# main_bottom.net
KiCad netlist of a schematic drawn in EAGLE
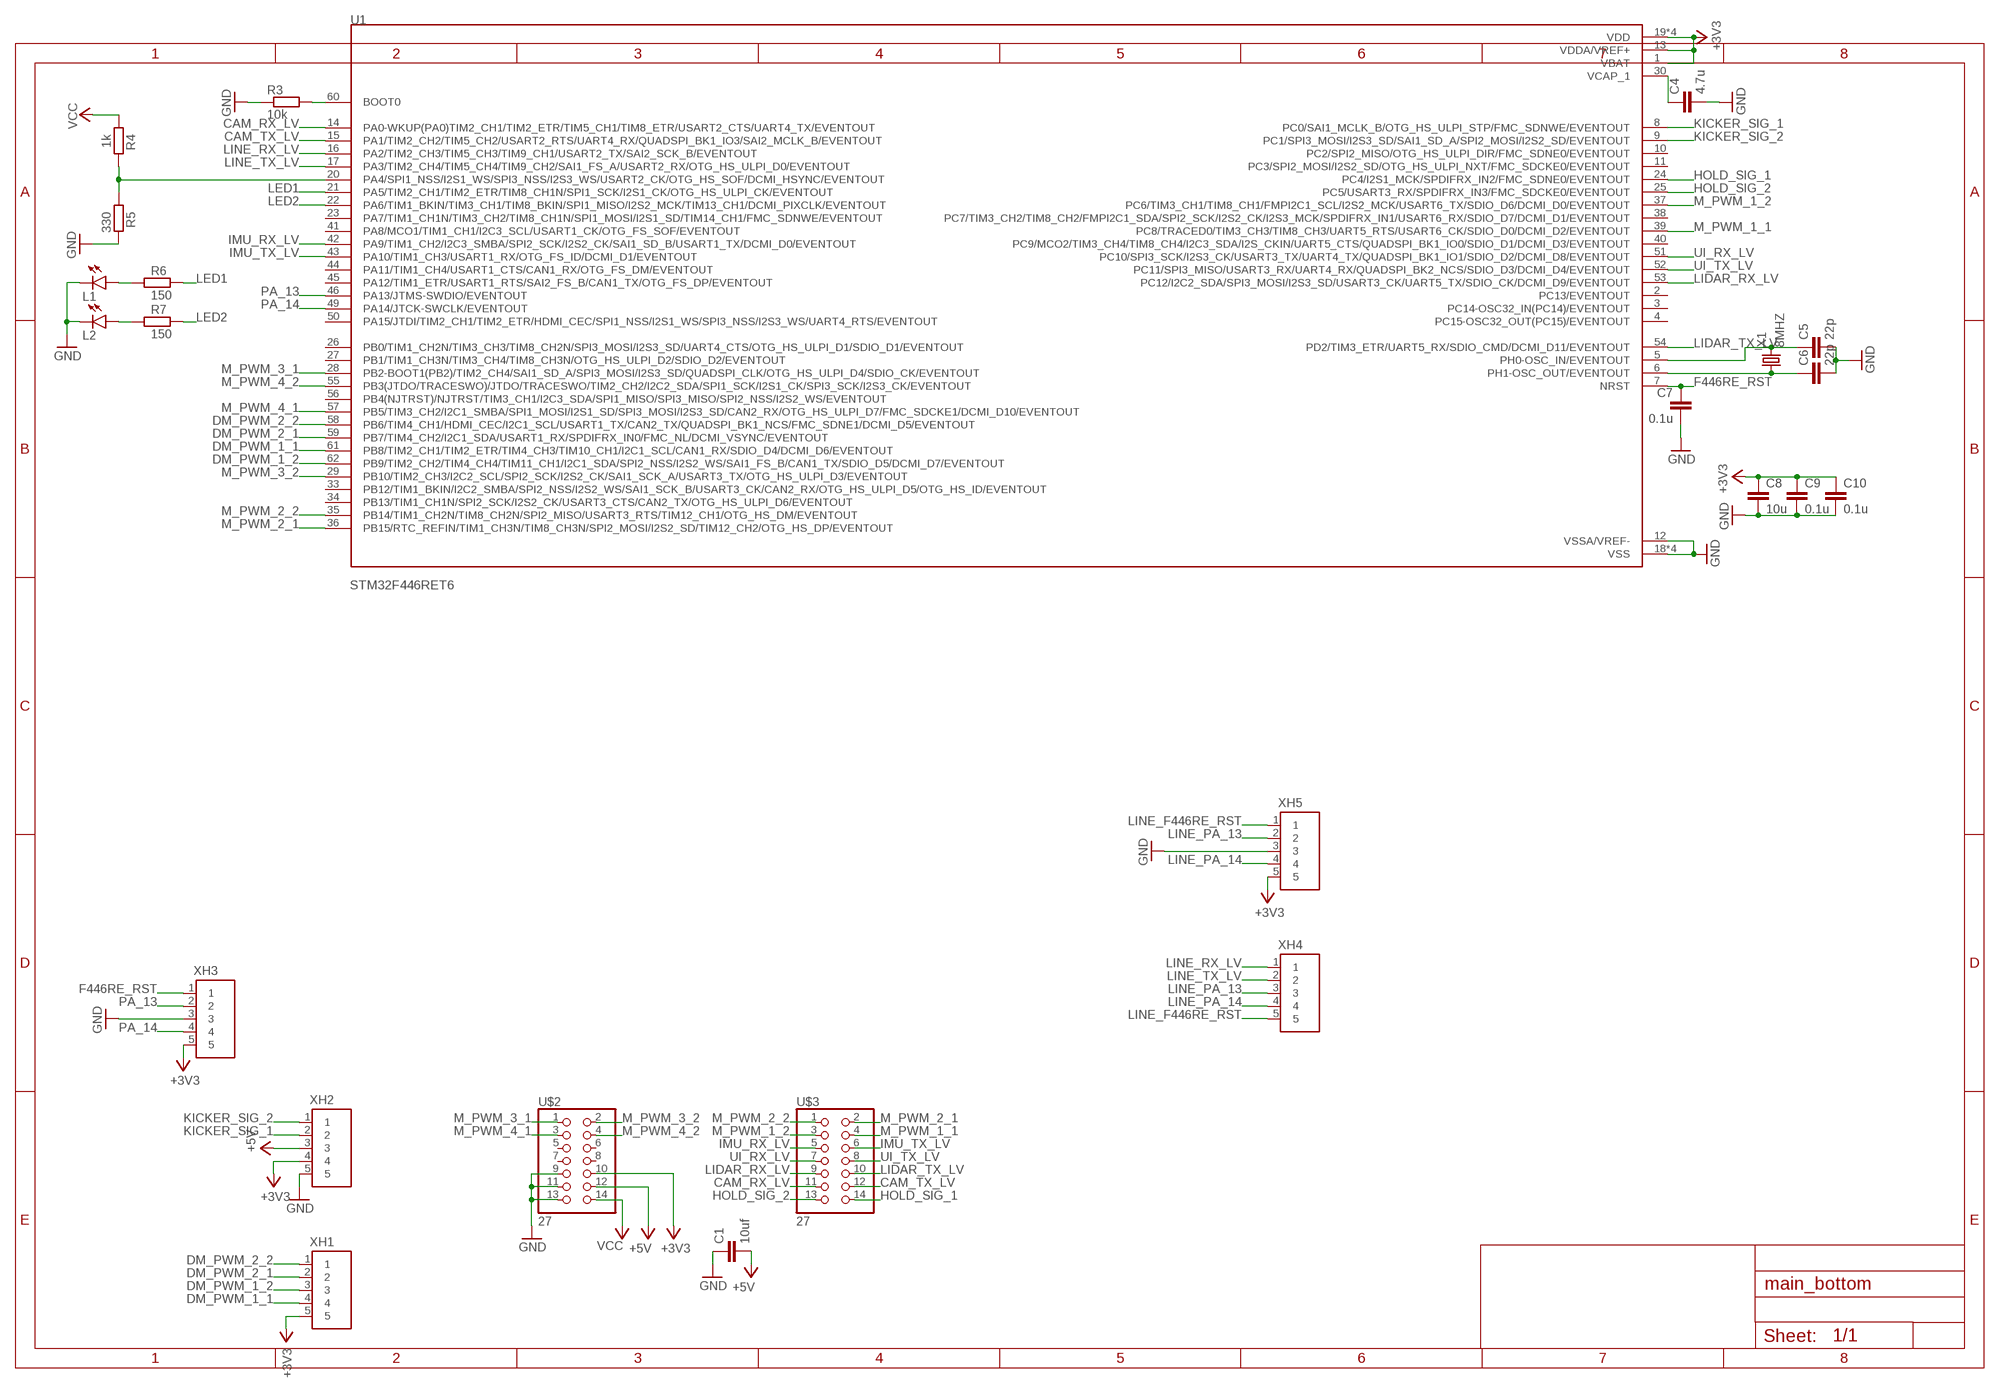
[diagram p0: schematic, sheet 1]

(export (version "E")
  (design (tool "Eeschema 10.0.6"))
  (components
    (comp (ref "C1")
      (value "10uf")
      (footprint "eagle-import:C0805")
      (libsource (lib "eagle-import") (part "C-EUC0805"))
    )
    (comp (ref "C4")
      (value "4.7u")
      (footprint "eagle-import:C0603")
      (libsource (lib "eagle-import") (part "C-EUC0603"))
    )
    (comp (ref "C5")
      (value "22p")
      (footprint "eagle-import:C0603")
      (libsource (lib "eagle-import") (part "C-EUC0603"))
    )
    (comp (ref "C6")
      (value "22p")
      (footprint "eagle-import:C0603")
      (libsource (lib "eagle-import") (part "C-EUC0603"))
    )
    (comp (ref "C7")
      (value "0.1u")
      (footprint "eagle-import:C0603")
      (libsource (lib "eagle-import") (part "C-EUC0603"))
    )
    (comp (ref "C8")
      (value "10u")
      (footprint "eagle-import:C0805")
      (libsource (lib "eagle-import") (part "C-EUC0805"))
    )
    (comp (ref "C9")
      (value "0.1u")
      (footprint "eagle-import:C0603")
      (libsource (lib "eagle-import") (part "C-EUC0603"))
    )
    (comp (ref "C10")
      (value "0.1u")
      (footprint "eagle-import:C0603")
      (libsource (lib "eagle-import") (part "C-EUC0603"))
    )
    (comp (ref "L1")
      (value "SML-E12P8WT86")
      (footprint "eagle-import:LED_SML-LXFM0603SIC-TR")
      (libsource (lib "eagle-import") (part "SML-E12P8WT86"))
    )
    (comp (ref "L2")
      (value "SML-E12P8WT86")
      (footprint "eagle-import:LED_SML-LXFM0603SIC-TR")
      (libsource (lib "eagle-import") (part "SML-E12P8WT86"))
    )
    (comp (ref "R3")
      (value "10k")
      (footprint "eagle-import:R0603")
      (libsource (lib "eagle-import") (part "R-EU_R0603"))
    )
    (comp (ref "R4")
      (value "1k")
      (footprint "eagle-import:R0603")
      (libsource (lib "eagle-import") (part "R-EU_R0603"))
    )
    (comp (ref "R5")
      (value "330")
      (footprint "eagle-import:R0603")
      (libsource (lib "eagle-import") (part "R-EU_R0603"))
    )
    (comp (ref "R6")
      (value "150")
      (footprint "eagle-import:R0603")
      (libsource (lib "eagle-import") (part "R-EU_R0603"))
    )
    (comp (ref "R7")
      (value "150")
      (footprint "eagle-import:R0603")
      (libsource (lib "eagle-import") (part "R-EU_R0603"))
    )
    (comp (ref "U$2")
      (value "27")
      (footprint "eagle-import:2_7")
      (libsource (lib "eagle-import") (part "27"))
    )
    (comp (ref "U$3")
      (value "27")
      (footprint "eagle-import:2_7")
      (libsource (lib "eagle-import") (part "27"))
    )
    (comp (ref "U1")
      (value "STM32F446RET6")
      (footprint "eagle-import:QFP50P1200X1200X160-64N")
      (fields (field (name "MF") "STMicroelectronics"))
      (libsource (lib "eagle-import") (part "STM32F446RET6"))
    )
    (comp (ref "X1")
      (value "8MHZ")
      (footprint "eagle-import:16MHZ")
      (libsource (lib "eagle-import") (part "16MHZ"))
    )
    (comp (ref "XH1")
      (value "S5B")
      (footprint "eagle-import:S5B")
      (libsource (lib "eagle-import") (part "S5B"))
    )
    (comp (ref "XH2")
      (value "S5B")
      (footprint "eagle-import:S5B")
      (libsource (lib "eagle-import") (part "S5B"))
    )
    (comp (ref "XH3")
      (value "S5B")
      (footprint "eagle-import:S5B")
      (libsource (lib "eagle-import") (part "S5B"))
    )
    (comp (ref "XH4")
      (value "S5B")
      (footprint "eagle-import:S5B")
      (libsource (lib "eagle-import") (part "S5B"))
    )
    (comp (ref "XH5")
      (value "S5B")
      (footprint "eagle-import:S5B")
      (libsource (lib "eagle-import") (part "S5B"))
    )
  )
  (nets
    (net (code "1") (name "+3V3") (class "Default")
      (node (ref "C10") (pin "1") (pinfunction "1_1") (pintype "passive"))
      (node (ref "C8") (pin "1") (pinfunction "1_1") (pintype "passive"))
      (node (ref "C9") (pin "1") (pinfunction "1_1") (pintype "passive"))
      (node (ref "U$2") (pin "10") (pinfunction "10_10") (pintype "passive"))
      (node (ref "U1") (pin "1") (pinfunction "VBAT_1") (pintype "power_in"))
      (node (ref "U1") (pin "13") (pinfunction "VDDA/VREF+_13") (pintype "power_in"))
      (node (ref "U1") (pin "19") (pinfunction "VDD_19") (pintype "power_in"))
      (node (ref "U1") (pin "32") (pinfunction "VDD_32") (pintype "power_in"))
      (node (ref "U1") (pin "48") (pinfunction "VDD_48") (pintype "power_in"))
      (node (ref "U1") (pin "64") (pinfunction "VDD_64") (pintype "power_in"))
      (node (ref "XH1") (pin "5") (pinfunction "5_5") (pintype "bidirectional"))
      (node (ref "XH2") (pin "4") (pinfunction "4_4") (pintype "bidirectional"))
      (node (ref "XH3") (pin "5") (pinfunction "5_5") (pintype "bidirectional"))
      (node (ref "XH5") (pin "5") (pinfunction "5_5") (pintype "bidirectional"))
    )
    (net (code "2") (name "+5V") (class "Default")
      (node (ref "C1") (pin "2") (pinfunction "2_2") (pintype "passive"))
      (node (ref "U$2") (pin "12") (pinfunction "12_12") (pintype "passive"))
      (node (ref "XH2") (pin "3") (pinfunction "3_3") (pintype "bidirectional"))
    )
    (net (code "3") (name "/CAM_RX_LV") (class "Default")
      (node (ref "U$3") (pin "11") (pinfunction "11_11") (pintype "passive"))
      (node (ref "U1") (pin "14") (pinfunction "PA0-WKUP(PA0)TIM2_CH1/TIM2_ETR/TIM5_CH1/TIM8_ETR/USART2_CTS/UART4_TX/EVENTOUT_14") (pintype "bidirectional"))
    )
    (net (code "4") (name "/CAM_TX_LV") (class "Default")
      (node (ref "U$3") (pin "12") (pinfunction "12_12") (pintype "passive"))
      (node (ref "U1") (pin "15") (pinfunction "PA1/TIM2_CH2/TIM5_CH2/USART2_RTS/UART4_RX/QUADSPI_BK1_IO3/SAI2_MCLK_B/EVENTOUT_15") (pintype "bidirectional"))
    )
    (net (code "5") (name "/DM_PWM_1_1") (class "Default")
      (node (ref "U1") (pin "61") (pinfunction "PB8/TIM2_CH1/TIM2_ETR/TIM4_CH3/TIM10_CH1/I2C1_SCL/CAN1_RX/SDIO_D4/DCMI_D6/EVENTOUT_61") (pintype "bidirectional"))
      (node (ref "XH1") (pin "4") (pinfunction "4_4") (pintype "bidirectional"))
    )
    (net (code "6") (name "/DM_PWM_1_2") (class "Default")
      (node (ref "U1") (pin "62") (pinfunction "PB9/TIM2_CH2/TIM4_CH4/TIM11_CH1/I2C1_SDA/SPI2_NSS/I2S2_WS/SAI1_FS_B/CAN1_TX/SDIO_D5/DCMI_D7/EVENTOUT_62") (pintype "bidirectional"))
      (node (ref "XH1") (pin "3") (pinfunction "3_3") (pintype "bidirectional"))
    )
    (net (code "7") (name "/DM_PWM_2_1") (class "Default")
      (node (ref "U1") (pin "59") (pinfunction "PB7/TIM4_CH2/I2C1_SDA/USART1_RX/SPDIFRX_IN0/FMC_NL/DCMI_VSYNC/EVENTOUT_59") (pintype "bidirectional"))
      (node (ref "XH1") (pin "2") (pinfunction "2_2") (pintype "bidirectional"))
    )
    (net (code "8") (name "/DM_PWM_2_2") (class "Default")
      (node (ref "U1") (pin "58") (pinfunction "PB6/TIM4_CH1/HDMI_CEC/I2C1_SCL/USART1_TX/CAN2_TX/QUADSPI_BK1_NCS/FMC_SDNE1/DCMI_D5/EVENTOUT_58") (pintype "bidirectional"))
      (node (ref "XH1") (pin "1") (pinfunction "1_1") (pintype "bidirectional"))
    )
    (net (code "9") (name "/F446RE_RST") (class "Default")
      (node (ref "C7") (pin "1") (pinfunction "1_1") (pintype "passive"))
      (node (ref "U1") (pin "7") (pinfunction "NRST_7") (pintype "bidirectional"))
      (node (ref "XH3") (pin "1") (pinfunction "1_1") (pintype "bidirectional"))
    )
    (net (code "10") (name "/HOLD_SIG_1") (class "Default")
      (node (ref "U$3") (pin "14") (pinfunction "14_14") (pintype "passive"))
      (node (ref "U1") (pin "24") (pinfunction "PC4/I2S1_MCK/SPDIFRX_IN2/FMC_SDNE0/EVENTOUT_24") (pintype "bidirectional"))
    )
    (net (code "11") (name "/HOLD_SIG_2") (class "Default")
      (node (ref "U$3") (pin "13") (pinfunction "13_13") (pintype "passive"))
      (node (ref "U1") (pin "25") (pinfunction "PC5/USART3_RX/SPDIFRX_IN3/FMC_SDCKE0/EVENTOUT_25") (pintype "bidirectional"))
    )
    (net (code "12") (name "/IMU_RX_LV") (class "Default")
      (node (ref "U$3") (pin "5") (pinfunction "5_5") (pintype "passive"))
      (node (ref "U1") (pin "42") (pinfunction "PA9/TIM1_CH2/I2C3_SMBA/SPI2_SCK/I2S2_CK/SAI1_SD_B/USART1_TX/DCMI_D0/EVENTOUT_42") (pintype "bidirectional"))
    )
    (net (code "13") (name "/IMU_TX_LV") (class "Default")
      (node (ref "U$3") (pin "6") (pinfunction "6_6") (pintype "passive"))
      (node (ref "U1") (pin "43") (pinfunction "PA10/TIM1_CH3/USART1_RX/OTG_FS_ID/DCMI_D1/EVENTOUT_43") (pintype "bidirectional"))
    )
    (net (code "14") (name "/KICKER_SIG_1") (class "Default")
      (node (ref "U1") (pin "8") (pinfunction "PC0/SAI1_MCLK_B/OTG_HS_ULPI_STP/FMC_SDNWE/EVENTOUT_8") (pintype "bidirectional"))
      (node (ref "XH2") (pin "2") (pinfunction "2_2") (pintype "bidirectional"))
    )
    (net (code "15") (name "/KICKER_SIG_2") (class "Default")
      (node (ref "U1") (pin "9") (pinfunction "PC1/SPI3_MOSI/I2S3_SD/SAI1_SD_A/SPI2_MOSI/I2S2_SD/EVENTOUT_9") (pintype "bidirectional"))
      (node (ref "XH2") (pin "1") (pinfunction "1_1") (pintype "bidirectional"))
    )
    (net (code "16") (name "/LED1") (class "Default")
      (node (ref "R6") (pin "2") (pinfunction "2_2") (pintype "passive"))
      (node (ref "U1") (pin "21") (pinfunction "PA5/TIM2_CH1/TIM2_ETR/TIM8_CH1N/SPI1_SCK/I2S1_CK/OTG_HS_ULPI_CK/EVENTOUT_21") (pintype "bidirectional"))
    )
    (net (code "17") (name "/LED2") (class "Default")
      (node (ref "R7") (pin "2") (pinfunction "2_2") (pintype "passive"))
      (node (ref "U1") (pin "22") (pinfunction "PA6/TIM1_BKIN/TIM3_CH1/TIM8_BKIN/SPI1_MISO/I2S2_MCK/TIM13_CH1/DCMI_PIXCLK/EVENTOUT_22") (pintype "bidirectional"))
    )
    (net (code "18") (name "/LIDAR_RX_LV") (class "Default")
      (node (ref "U$3") (pin "9") (pinfunction "9_9") (pintype "passive"))
      (node (ref "U1") (pin "53") (pinfunction "PC12/I2C2_SDA/SPI3_MOSI/I2S3_SD/USART3_CK/UART5_TX/SDIO_CK/DCMI_D9/EVENTOUT_53") (pintype "bidirectional"))
    )
    (net (code "19") (name "/LIDAR_TX_LV") (class "Default")
      (node (ref "U$3") (pin "10") (pinfunction "10_10") (pintype "passive"))
      (node (ref "U1") (pin "54") (pinfunction "PD2/TIM3_ETR/UART5_RX/SDIO_CMD/DCMI_D11/EVENTOUT_54") (pintype "bidirectional"))
    )
    (net (code "20") (name "/LINE_F446RE_RST") (class "Default")
      (node (ref "XH4") (pin "5") (pinfunction "5_5") (pintype "bidirectional"))
      (node (ref "XH5") (pin "1") (pinfunction "1_1") (pintype "bidirectional"))
    )
    (net (code "21") (name "/LINE_PA_13") (class "Default")
      (node (ref "XH4") (pin "3") (pinfunction "3_3") (pintype "bidirectional"))
      (node (ref "XH5") (pin "2") (pinfunction "2_2") (pintype "bidirectional"))
    )
    (net (code "22") (name "/LINE_PA_14") (class "Default")
      (node (ref "XH4") (pin "4") (pinfunction "4_4") (pintype "bidirectional"))
      (node (ref "XH5") (pin "4") (pinfunction "4_4") (pintype "bidirectional"))
    )
    (net (code "23") (name "/LINE_RX_LV") (class "Default")
      (node (ref "U1") (pin "16") (pinfunction "PA2/TIM2_CH3/TIM5_CH3/TIM9_CH1/USART2_TX/SAI2_SCK_B/EVENTOUT_16") (pintype "bidirectional"))
      (node (ref "XH4") (pin "1") (pinfunction "1_1") (pintype "bidirectional"))
    )
    (net (code "24") (name "/LINE_TX_LV") (class "Default")
      (node (ref "U1") (pin "17") (pinfunction "PA3/TIM2_CH4/TIM5_CH4/TIM9_CH2/SAI1_FS_A/USART2_RX/OTG_HS_ULPI_D0/EVENTOUT_17") (pintype "bidirectional"))
      (node (ref "XH4") (pin "2") (pinfunction "2_2") (pintype "bidirectional"))
    )
    (net (code "25") (name "/M_PWM_1_1") (class "Default")
      (node (ref "U$3") (pin "4") (pinfunction "4_4") (pintype "passive"))
      (node (ref "U1") (pin "39") (pinfunction "PC8/TRACED0/TIM3_CH3/TIM8_CH3/UART5_RTS/USART6_CK/SDIO_D0/DCMI_D2/EVENTOUT_39") (pintype "bidirectional"))
    )
    (net (code "26") (name "/M_PWM_1_2") (class "Default")
      (node (ref "U$3") (pin "3") (pinfunction "3_3") (pintype "passive"))
      (node (ref "U1") (pin "37") (pinfunction "PC6/TIM3_CH1/TIM8_CH1/FMPI2C1_SCL/I2S2_MCK/USART6_TX/SDIO_D6/DCMI_D0/EVENTOUT_37") (pintype "bidirectional"))
    )
    (net (code "27") (name "/M_PWM_2_1") (class "Default")
      (node (ref "U$3") (pin "2") (pinfunction "2_2") (pintype "passive"))
      (node (ref "U1") (pin "36") (pinfunction "PB15/RTC_REFIN/TIM1_CH3N/TIM8_CH3N/SPI2_MOSI/I2S2_SD/TIM12_CH2/OTG_HS_DP/EVENTOUT_36") (pintype "bidirectional"))
    )
    (net (code "28") (name "/M_PWM_2_2") (class "Default")
      (node (ref "U$3") (pin "1") (pinfunction "1_1") (pintype "passive"))
      (node (ref "U1") (pin "35") (pinfunction "PB14/TIM1_CH2N/TIM8_CH2N/SPI2_MISO/USART3_RTS/TIM12_CH1/OTG_HS_DM/EVENTOUT_35") (pintype "bidirectional"))
    )
    (net (code "29") (name "/M_PWM_3_1") (class "Default")
      (node (ref "U$2") (pin "1") (pinfunction "1_1") (pintype "passive"))
      (node (ref "U1") (pin "28") (pinfunction "PB2-BOOT1(PB2)/TIM2_CH4/SAI1_SD_A/SPI3_MOSI/I2S3_SD/QUADSPI_CLK/OTG_HS_ULPI_D4/SDIO_CK/EVENTOUT_28") (pintype "bidirectional"))
    )
    (net (code "30") (name "/M_PWM_3_2") (class "Default")
      (node (ref "U$2") (pin "2") (pinfunction "2_2") (pintype "passive"))
      (node (ref "U1") (pin "29") (pinfunction "PB10/TIM2_CH3/I2C2_SCL/SPI2_SCK/I2S2_CK/SAI1_SCK_A/USART3_TX/OTG_HS_ULPI_D3/EVENTOUT_29") (pintype "bidirectional"))
    )
    (net (code "31") (name "/M_PWM_4_1") (class "Default")
      (node (ref "U$2") (pin "3") (pinfunction "3_3") (pintype "passive"))
      (node (ref "U1") (pin "57") (pinfunction "PB5/TIM3_CH2/I2C1_SMBA/SPI1_MOSI/I2S1_SD/SPI3_MOSI/I2S3_SD/CAN2_RX/OTG_HS_ULPI_D7/FMC_SDCKE1/DCMI_D10/EVENTOUT_57") (pintype "bidirectional"))
    )
    (net (code "32") (name "/M_PWM_4_2") (class "Default")
      (node (ref "U$2") (pin "4") (pinfunction "4_4") (pintype "passive"))
      (node (ref "U1") (pin "55") (pinfunction "PB3(JTDO/TRACESWO)/JTDO/TRACESWO/TIM2_CH2/I2C2_SDA/SPI1_SCK/I2S1_CK/SPI3_SCK/I2S3_CK/EVENTOUT_55") (pintype "bidirectional"))
    )
    (net (code "33") (name "/PA_13") (class "Default")
      (node (ref "U1") (pin "46") (pinfunction "PA13/JTMS-SWDIO/EVENTOUT_46") (pintype "bidirectional"))
      (node (ref "XH3") (pin "2") (pinfunction "2_2") (pintype "bidirectional"))
    )
    (net (code "34") (name "/PA_14") (class "Default")
      (node (ref "U1") (pin "49") (pinfunction "PA14/JTCK-SWCLK/EVENTOUT_49") (pintype "bidirectional"))
      (node (ref "XH3") (pin "4") (pinfunction "4_4") (pintype "bidirectional"))
    )
    (net (code "35") (name "/UI_RX_LV") (class "Default")
      (node (ref "U$3") (pin "7") (pinfunction "7_7") (pintype "passive"))
      (node (ref "U1") (pin "51") (pinfunction "PC10/SPI3_SCK/I2S3_CK/USART3_TX/UART4_TX/QUADSPI_BK1_IO1/SDIO_D2/DCMI_D8/EVENTOUT_51") (pintype "bidirectional"))
    )
    (net (code "36") (name "/UI_TX_LV") (class "Default")
      (node (ref "U$3") (pin "8") (pinfunction "8_8") (pintype "passive"))
      (node (ref "U1") (pin "52") (pinfunction "PC11/SPI3_MISO/USART3_RX/UART4_RX/QUADSPI_BK2_NCS/SDIO_D3/DCMI_D4/EVENTOUT_52") (pintype "bidirectional"))
    )
    (net (code "37") (name "GND") (class "Default")
      (node (ref "C1") (pin "1") (pinfunction "1_1") (pintype "passive"))
      (node (ref "C10") (pin "2") (pinfunction "2_2") (pintype "passive"))
      (node (ref "C4") (pin "2") (pinfunction "2_2") (pintype "passive"))
      (node (ref "C5") (pin "2") (pinfunction "2_2") (pintype "passive"))
      (node (ref "C6") (pin "2") (pinfunction "2_2") (pintype "passive"))
      (node (ref "C7") (pin "2") (pinfunction "2_2") (pintype "passive"))
      (node (ref "C8") (pin "2") (pinfunction "2_2") (pintype "passive"))
      (node (ref "C9") (pin "2") (pinfunction "2_2") (pintype "passive"))
      (node (ref "L1") (pin "C") (pinfunction "C_C") (pintype "passive"))
      (node (ref "L2") (pin "C") (pinfunction "C_C") (pintype "passive"))
      (node (ref "R3") (pin "1") (pinfunction "1_1") (pintype "passive"))
      (node (ref "R5") (pin "2") (pinfunction "2_2") (pintype "passive"))
      (node (ref "U$2") (pin "11") (pinfunction "11_11") (pintype "passive"))
      (node (ref "U$2") (pin "13") (pinfunction "13_13") (pintype "passive"))
      (node (ref "U$2") (pin "9") (pinfunction "9_9") (pintype "passive"))
      (node (ref "U1") (pin "12") (pinfunction "VSSA/VREF-_12") (pintype "power_in"))
      (node (ref "U1") (pin "18") (pinfunction "VSS_18") (pintype "power_in"))
      (node (ref "U1") (pin "31") (pinfunction "VSS_31") (pintype "power_in"))
      (node (ref "U1") (pin "47") (pinfunction "VSS_47") (pintype "power_in"))
      (node (ref "U1") (pin "63") (pinfunction "VSS_63") (pintype "power_in"))
      (node (ref "XH2") (pin "5") (pinfunction "5_5") (pintype "bidirectional"))
      (node (ref "XH3") (pin "3") (pinfunction "3_3") (pintype "bidirectional"))
      (node (ref "XH5") (pin "3") (pinfunction "3_3") (pintype "bidirectional"))
    )
    (net (code "38") (name "Net-(L1-PadA)") (class "Default")
      (node (ref "L1") (pin "A") (pinfunction "A_A") (pintype "passive"))
      (node (ref "R6") (pin "1") (pinfunction "1_1") (pintype "passive"))
    )
    (net (code "39") (name "Net-(L2-PadA)") (class "Default")
      (node (ref "L2") (pin "A") (pinfunction "A_A") (pintype "passive"))
      (node (ref "R7") (pin "1") (pinfunction "1_1") (pintype "passive"))
    )
    (net (code "40") (name "Net-(U1-BOOT0)") (class "Default")
      (node (ref "R3") (pin "2") (pinfunction "2_2") (pintype "passive"))
      (node (ref "U1") (pin "60") (pinfunction "BOOT0_60") (pintype "input"))
    )
    (net (code "41") (name "Net-(U1-PA4{slash}SPI1_NSS{slash}I2S1_WS{slash}SPI3_NSS{slash}I2S3_WS{slash}USART2_CK{slash}OTG_HS_SOF{slash}DCMI_HSYNC{slash}EVENTOUT)") (class "Default")
      (node (ref "R4") (pin "2") (pinfunction "2_2") (pintype "passive"))
      (node (ref "R5") (pin "1") (pinfunction "1_1") (pintype "passive"))
      (node (ref "U1") (pin "20") (pinfunction "PA4/SPI1_NSS/I2S1_WS/SPI3_NSS/I2S3_WS/USART2_CK/OTG_HS_SOF/DCMI_HSYNC/EVENTOUT_20") (pintype "bidirectional"))
    )
    (net (code "42") (name "Net-(U1-PH0-OSC_IN{slash}EVENTOUT)") (class "Default")
      (node (ref "C5") (pin "1") (pinfunction "1_1") (pintype "passive"))
      (node (ref "U1") (pin "5") (pinfunction "PH0-OSC_IN/EVENTOUT_5") (pintype "bidirectional"))
      (node (ref "X1") (pin "P$2") (pinfunction "2_P$2") (pintype "passive"))
    )
    (net (code "43") (name "Net-(U1-PH1-OSC_OUT{slash}EVENTOUT)") (class "Default")
      (node (ref "C6") (pin "1") (pinfunction "1_1") (pintype "passive"))
      (node (ref "U1") (pin "6") (pinfunction "PH1-OSC_OUT/EVENTOUT_6") (pintype "bidirectional"))
      (node (ref "X1") (pin "P$1") (pinfunction "1_P$1") (pintype "passive"))
    )
    (net (code "44") (name "Net-(U1-VCAP_1)") (class "Default")
      (node (ref "C4") (pin "1") (pinfunction "1_1") (pintype "passive"))
      (node (ref "U1") (pin "30") (pinfunction "VCAP_1_30") (pintype "power_in"))
    )
    (net (code "45") (name "VCC") (class "Default")
      (node (ref "R4") (pin "1") (pinfunction "1_1") (pintype "passive"))
      (node (ref "U$2") (pin "14") (pinfunction "14_14") (pintype "passive"))
    )
    (net (code "46") (name "unconnected-(U$2-Pad5)") (class "Default")
      (node (ref "U$2") (pin "5") (pinfunction "5_5") (pintype "passive"))
    )
    (net (code "47") (name "unconnected-(U$2-Pad6)") (class "Default")
      (node (ref "U$2") (pin "6") (pinfunction "6_6") (pintype "passive"))
    )
    (net (code "48") (name "unconnected-(U$2-Pad7)") (class "Default")
      (node (ref "U$2") (pin "7") (pinfunction "7_7") (pintype "passive"))
    )
    (net (code "49") (name "unconnected-(U$2-Pad8)") (class "Default")
      (node (ref "U$2") (pin "8") (pinfunction "8_8") (pintype "passive"))
    )
    (net (code "50") (name "unconnected-(U1-PA7{slash}TIM1_CH1N{slash}TIM3_CH2{slash}TIM8_CH1N{slash}SPI1_MOSI{slash}I2S1_SD{slash}TIM14_CH1{slash}FMC_SDNWE{slash}EVENTOUT-Pad23)") (class "Default")
      (node (ref "U1") (pin "23") (pinfunction "PA7/TIM1_CH1N/TIM3_CH2/TIM8_CH1N/SPI1_MOSI/I2S1_SD/TIM14_CH1/FMC_SDNWE/EVENTOUT_23") (pintype "bidirectional"))
    )
    (net (code "51") (name "unconnected-(U1-PA8{slash}MCO1{slash}TIM1_CH1{slash}I2C3_SCL{slash}USART1_CK{slash}OTG_FS_SOF{slash}EVENTOUT-Pad41)") (class "Default")
      (node (ref "U1") (pin "41") (pinfunction "PA8/MCO1/TIM1_CH1/I2C3_SCL/USART1_CK/OTG_FS_SOF/EVENTOUT_41") (pintype "bidirectional"))
    )
    (net (code "52") (name "unconnected-(U1-PA11{slash}TIM1_CH4{slash}USART1_CTS{slash}CAN1_RX{slash}OTG_FS_DM{slash}EVENTOUT-Pad44)") (class "Default")
      (node (ref "U1") (pin "44") (pinfunction "PA11/TIM1_CH4/USART1_CTS/CAN1_RX/OTG_FS_DM/EVENTOUT_44") (pintype "bidirectional"))
    )
    (net (code "53") (name "unconnected-(U1-PA12{slash}TIM1_ETR{slash}USART1_RTS{slash}SAI2_FS_B{slash}CAN1_TX{slash}OTG_FS_DP{slash}EVENTOUT-Pad45)") (class "Default")
      (node (ref "U1") (pin "45") (pinfunction "PA12/TIM1_ETR/USART1_RTS/SAI2_FS_B/CAN1_TX/OTG_FS_DP/EVENTOUT_45") (pintype "bidirectional"))
    )
    (net (code "54") (name "unconnected-(U1-PA15{slash}JTDI{slash}TIM2_CH1{slash}TIM2_ETR{slash}HDMI_CEC{slash}SPI1_NSS{slash}I2S1_WS{slash}SPI3_NSS{slash}I2S3_WS{slash}UART4_RTS{slash}EVENTOUT-Pad50)") (class "Default")
      (node (ref "U1") (pin "50") (pinfunction "PA15/JTDI/TIM2_CH1/TIM2_ETR/HDMI_CEC/SPI1_NSS/I2S1_WS/SPI3_NSS/I2S3_WS/UART4_RTS/EVENTOUT_50") (pintype "bidirectional"))
    )
    (net (code "55") (name "unconnected-(U1-PB0{slash}TIM1_CH2N{slash}TIM3_CH3{slash}TIM8_CH2N{slash}SPI3_MOSI{slash}I2S3_SD{slash}UART4_CTS{slash}OTG_HS_ULPI_D1{slash}SDIO_D1{slash}EVENTOUT-Pad26)") (class "Default")
      (node (ref "U1") (pin "26") (pinfunction "PB0/TIM1_CH2N/TIM3_CH3/TIM8_CH2N/SPI3_MOSI/I2S3_SD/UART4_CTS/OTG_HS_ULPI_D1/SDIO_D1/EVENTOUT_26") (pintype "bidirectional"))
    )
    (net (code "56") (name "unconnected-(U1-PB1{slash}TIM1_CH3N{slash}TIM3_CH4{slash}TIM8_CH3N{slash}OTG_HS_ULPI_D2{slash}SDIO_D2{slash}EVENTOUT-Pad27)") (class "Default")
      (node (ref "U1") (pin "27") (pinfunction "PB1/TIM1_CH3N/TIM3_CH4/TIM8_CH3N/OTG_HS_ULPI_D2/SDIO_D2/EVENTOUT_27") (pintype "bidirectional"))
    )
    (net (code "57") (name "unconnected-(U1-PB4(NJTRST){slash}NJTRST{slash}TIM3_CH1{slash}I2C3_SDA{slash}SPI1_MISO{slash}SPI3_MISO{slash}SPI2_NSS{slash}I2S2_WS{slash}EVENTOUT-Pad56)") (class "Default")
      (node (ref "U1") (pin "56") (pinfunction "PB4(NJTRST)/NJTRST/TIM3_CH1/I2C3_SDA/SPI1_MISO/SPI3_MISO/SPI2_NSS/I2S2_WS/EVENTOUT_56") (pintype "bidirectional"))
    )
    (net (code "58") (name "unconnected-(U1-PB12{slash}TIM1_BKIN{slash}I2C2_SMBA{slash}SPI2_NSS{slash}I2S2_WS{slash}SAI1_SCK_B{slash}USART3_CK{slash}CAN2_RX{slash}OTG_HS_ULPI_D5{slash}OTG_HS_ID{slash}EVENTOUT-Pad33)") (class "Default")
      (node (ref "U1") (pin "33") (pinfunction "PB12/TIM1_BKIN/I2C2_SMBA/SPI2_NSS/I2S2_WS/SAI1_SCK_B/USART3_CK/CAN2_RX/OTG_HS_ULPI_D5/OTG_HS_ID/EVENTOUT_33") (pintype "bidirectional"))
    )
    (net (code "59") (name "unconnected-(U1-PB13{slash}TIM1_CH1N{slash}SPI2_SCK{slash}I2S2_CK{slash}USART3_CTS{slash}CAN2_TX{slash}OTG_HS_ULPI_D6{slash}EVENTOUT-Pad34)") (class "Default")
      (node (ref "U1") (pin "34") (pinfunction "PB13/TIM1_CH1N/SPI2_SCK/I2S2_CK/USART3_CTS/CAN2_TX/OTG_HS_ULPI_D6/EVENTOUT_34") (pintype "bidirectional"))
    )
    (net (code "60") (name "unconnected-(U1-PC2{slash}SPI2_MISO{slash}OTG_HS_ULPI_DIR{slash}FMC_SDNE0{slash}EVENTOUT-Pad10)") (class "Default")
      (node (ref "U1") (pin "10") (pinfunction "PC2/SPI2_MISO/OTG_HS_ULPI_DIR/FMC_SDNE0/EVENTOUT_10") (pintype "bidirectional"))
    )
    (net (code "61") (name "unconnected-(U1-PC3{slash}SPI2_MOSI{slash}I2S2_SD{slash}OTG_HS_ULPI_NXT{slash}FMC_SDCKE0{slash}EVENTOUT-Pad11)") (class "Default")
      (node (ref "U1") (pin "11") (pinfunction "PC3/SPI2_MOSI/I2S2_SD/OTG_HS_ULPI_NXT/FMC_SDCKE0/EVENTOUT_11") (pintype "bidirectional"))
    )
    (net (code "62") (name "unconnected-(U1-PC7{slash}TIM3_CH2{slash}TIM8_CH2{slash}FMPI2C1_SDA{slash}SPI2_SCK{slash}I2S2_CK{slash}I2S3_MCK{slash}SPDIFRX_IN1{slash}USART6_RX{slash}SDIO_D7{slash}DCMI_D1{slash}EVENTOUT-Pad38)") (class "Default")
      (node (ref "U1") (pin "38") (pinfunction "PC7/TIM3_CH2/TIM8_CH2/FMPI2C1_SDA/SPI2_SCK/I2S2_CK/I2S3_MCK/SPDIFRX_IN1/USART6_RX/SDIO_D7/DCMI_D1/EVENTOUT_38") (pintype "bidirectional"))
    )
    (net (code "63") (name "unconnected-(U1-PC9{slash}MCO2{slash}TIM3_CH4{slash}TIM8_CH4{slash}I2C3_SDA{slash}I2S_CKIN{slash}UART5_CTS{slash}QUADSPI_BK1_IO0{slash}SDIO_D1{slash}DCMI_D3{slash}EVENTOUT-Pad40)") (class "Default")
      (node (ref "U1") (pin "40") (pinfunction "PC9/MCO2/TIM3_CH4/TIM8_CH4/I2C3_SDA/I2S_CKIN/UART5_CTS/QUADSPI_BK1_IO0/SDIO_D1/DCMI_D3/EVENTOUT_40") (pintype "bidirectional"))
    )
    (net (code "64") (name "unconnected-(U1-PC13{slash}EVENTOUT-Pad2)") (class "Default")
      (node (ref "U1") (pin "2") (pinfunction "PC13/EVENTOUT_2") (pintype "bidirectional"))
    )
    (net (code "65") (name "unconnected-(U1-PC14-OSC32_IN(PC14){slash}EVENTOUT-Pad3)") (class "Default")
      (node (ref "U1") (pin "3") (pinfunction "PC14-OSC32_IN(PC14)/EVENTOUT_3") (pintype "bidirectional"))
    )
    (net (code "66") (name "unconnected-(U1-PC15-OSC32_OUT(PC15){slash}EVENTOUT-Pad4)") (class "Default")
      (node (ref "U1") (pin "4") (pinfunction "PC15-OSC32_OUT(PC15)/EVENTOUT_4") (pintype "bidirectional"))
    )
  )
)
